# EtherWiz.net
KiCad netlist of a schematic drawn in Altium Designer
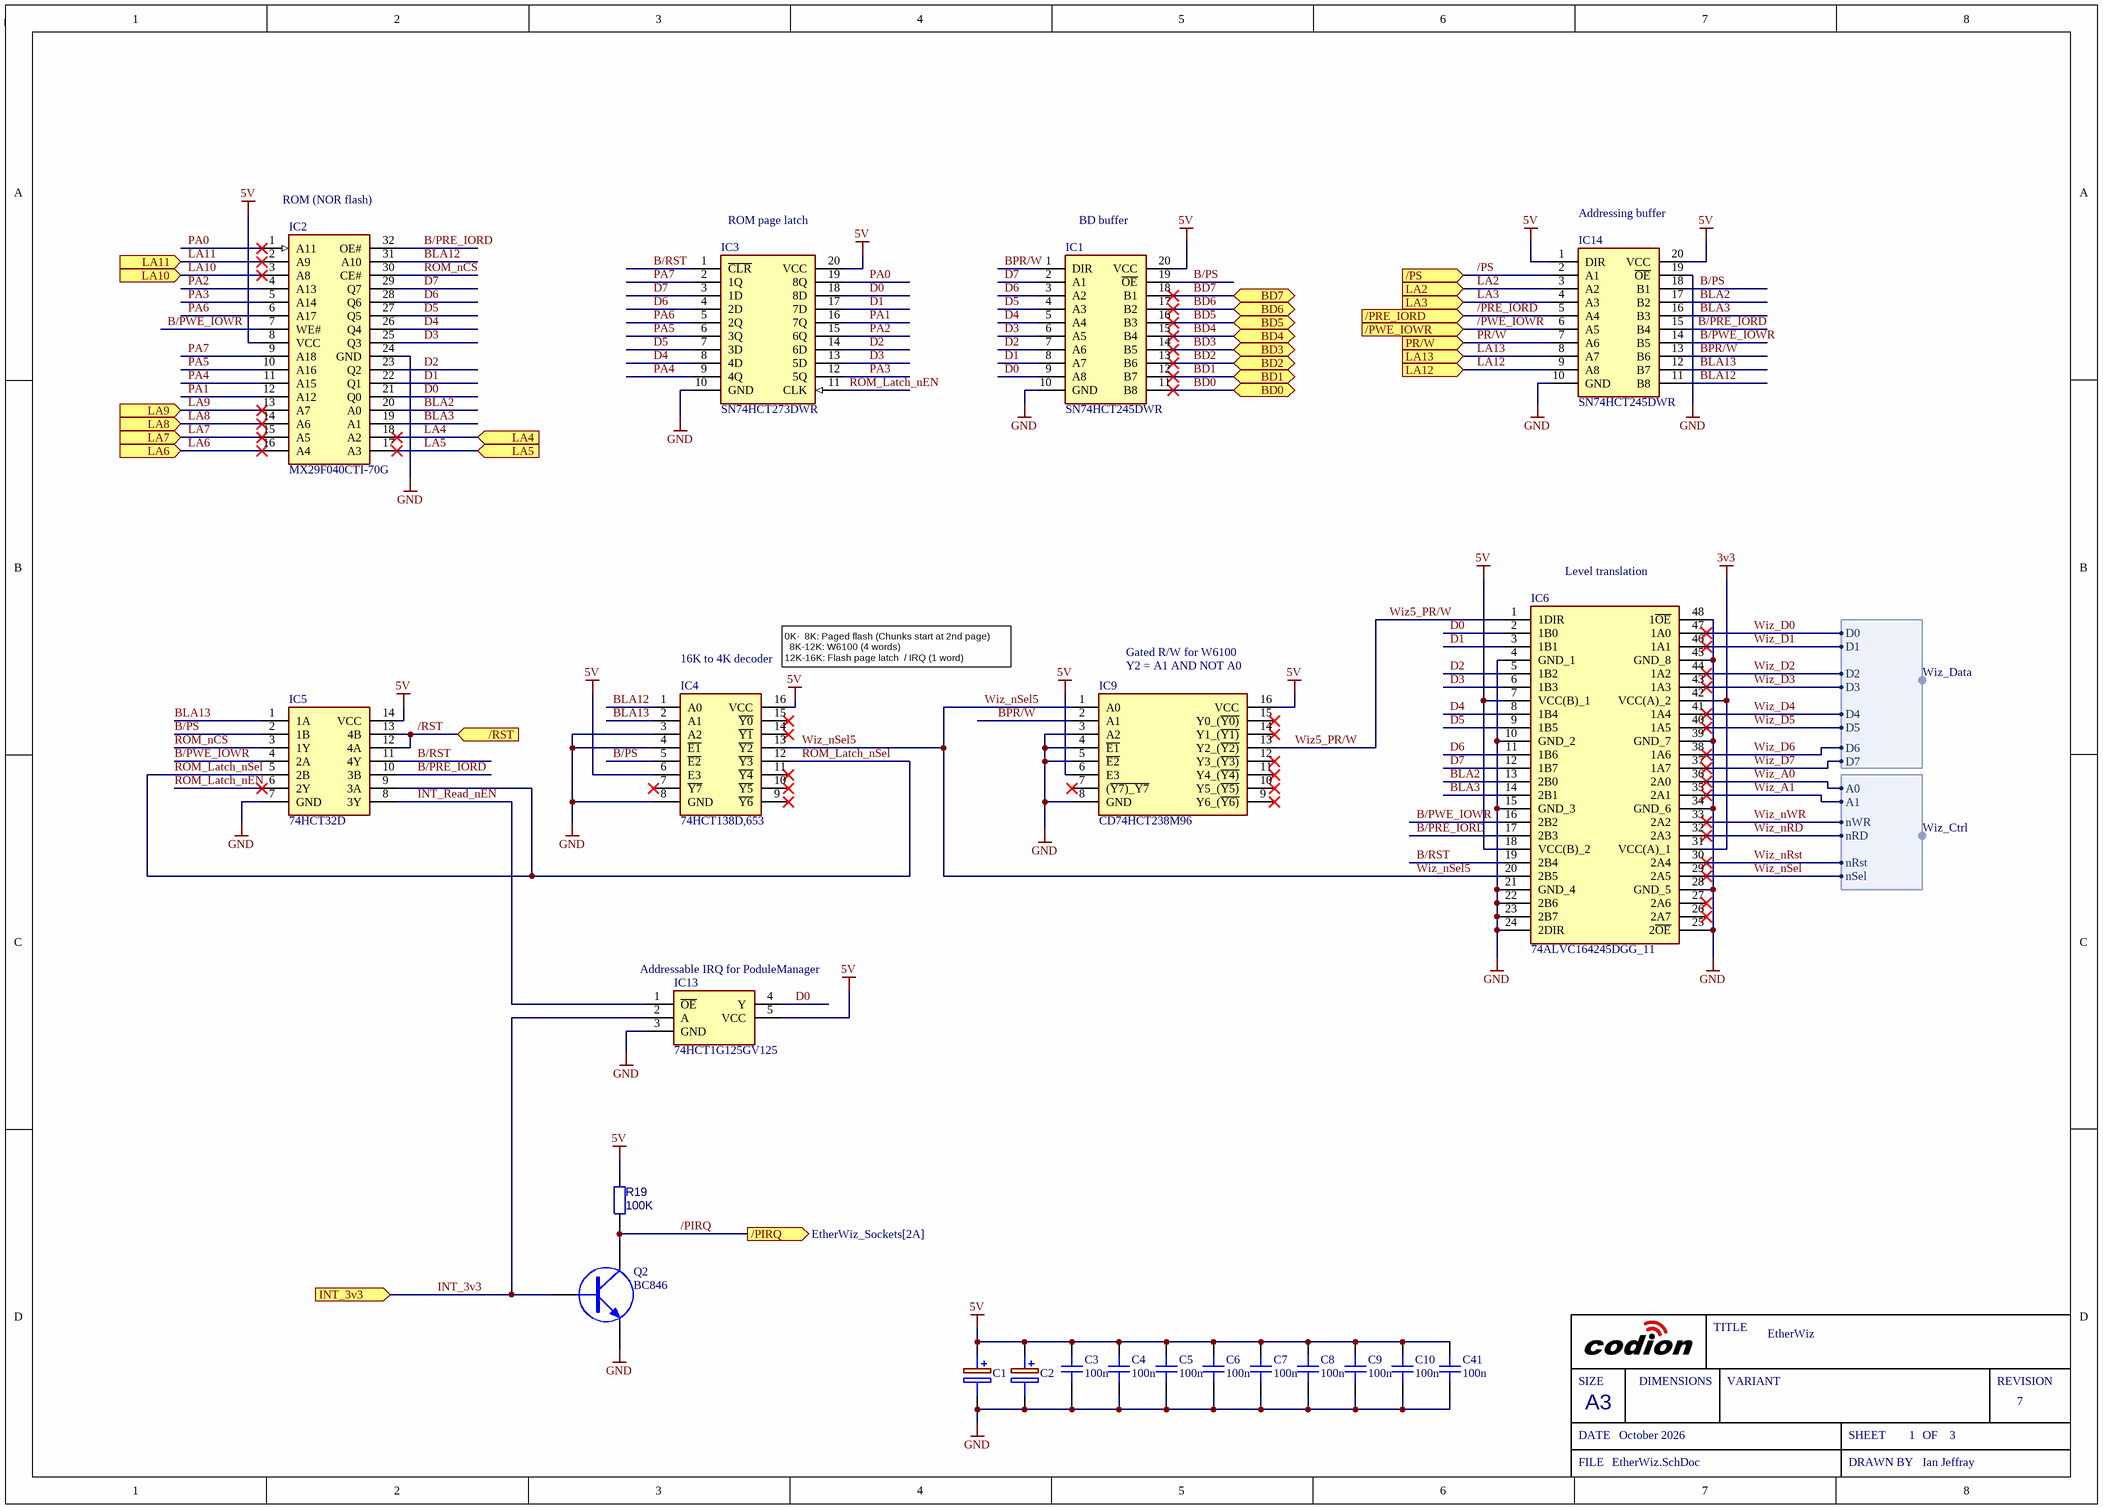
[diagram p0: EtherWiz.SchDoc]

(export (version "E")
  (design (tool "Eeschema 10.0.6"))
  (components
    (comp (ref "C1")
      (value "EEE-HA1C470AP")
      (footprint "SamacSys:EEE1AA101SP")
      (description "Capacitor Polarised")
      (fields (field (name "MOUSER PART NUMBER") "667-EEE-HA1C470AP"))
      (libsource (lib "*") (part "EEE-HA1C470AP"))
    )
    (comp (ref "C2")
      (value "EEE-HA1C470AP")
      (footprint "SamacSys:EEE1AA101SP")
      (description "Capacitor Polarised")
      (fields (field (name "MOUSER PART NUMBER") "667-EEE-HA1C470AP"))
      (libsource (lib "*") (part "EEE-HA1C470AP"))
    )
    (comp (ref "C3")
      (value "100n")
      (footprint "CAPC1608L")
      (description "CAP 100nF, 0603, 50V, X7R, 10%")
      (fields
        (field (name "DISTRIBUTOR1 PART NO") "CL10B104KB8NNNC")
        (field (name "DISTRIBUTOR2 PART NO") "311-1344-2-ND")
      )
      (libsource (lib "MCP1002_RevC") (part "CAP_100n_0603_50V_0"))
    )
    (comp (ref "C4")
      (value "100n")
      (footprint "CAPC1608L")
      (description "CAP 100nF, 0603, 50V, X7R, 10%")
      (fields
        (field (name "DISTRIBUTOR1 PART NO") "CL10B104KB8NNNC")
        (field (name "DISTRIBUTOR2 PART NO") "311-1344-2-ND")
      )
      (libsource (lib "MCP1002_RevC") (part "CAP_100n_0603_50V_0"))
    )
    (comp (ref "C5")
      (value "100n")
      (footprint "CAPC1608L")
      (description "CAP 100nF, 0603, 50V, X7R, 10%")
      (fields
        (field (name "DISTRIBUTOR1 PART NO") "CL10B104KB8NNNC")
        (field (name "DISTRIBUTOR2 PART NO") "311-1344-2-ND")
      )
      (libsource (lib "MCP1002_RevC") (part "CAP_100n_0603_50V_0"))
    )
    (comp (ref "C6")
      (value "100n")
      (footprint "CAPC1608L")
      (description "CAP 100nF, 0603, 50V, X7R, 10%")
      (fields
        (field (name "DISTRIBUTOR1 PART NO") "CL10B104KB8NNNC")
        (field (name "DISTRIBUTOR2 PART NO") "311-1344-2-ND")
      )
      (libsource (lib "MCP1002_RevC") (part "CAP_100n_0603_50V_0"))
    )
    (comp (ref "C7")
      (value "100n")
      (footprint "CAPC1608L")
      (description "CAP 100nF, 0603, 50V, X7R, 10%")
      (fields
        (field (name "DISTRIBUTOR1 PART NO") "CL10B104KB8NNNC")
        (field (name "DISTRIBUTOR2 PART NO") "311-1344-2-ND")
      )
      (libsource (lib "MCP1002_RevC") (part "CAP_100n_0603_50V_0"))
    )
    (comp (ref "C8")
      (value "100n")
      (footprint "CAPC1608L")
      (description "CAP 100nF, 0603, 50V, X7R, 10%")
      (fields
        (field (name "DISTRIBUTOR1 PART NO") "CL10B104KB8NNNC")
        (field (name "DISTRIBUTOR2 PART NO") "311-1344-2-ND")
      )
      (libsource (lib "MCP1002_RevC") (part "CAP_100n_0603_50V_0"))
    )
    (comp (ref "C9")
      (value "100n")
      (footprint "CAPC1608L")
      (description "CAP 100nF, 0603, 50V, X7R, 10%")
      (fields
        (field (name "DISTRIBUTOR1 PART NO") "CL10B104KB8NNNC")
        (field (name "DISTRIBUTOR2 PART NO") "311-1344-2-ND")
      )
      (libsource (lib "MCP1002_RevC") (part "CAP_100n_0603_50V_0"))
    )
    (comp (ref "C10")
      (value "100n")
      (footprint "CAPC1608L")
      (description "CAP 100nF, 0603, 50V, X7R, 10%")
      (fields
        (field (name "DISTRIBUTOR1 PART NO") "CL10B104KB8NNNC")
        (field (name "DISTRIBUTOR2 PART NO") "311-1344-2-ND")
      )
      (libsource (lib "MCP1002_RevC") (part "CAP_100n_0603_50V_0"))
    )
    (comp (ref "C41")
      (value "100n")
      (footprint "CAPC1608L")
      (description "CAP 100nF, 0603, 50V, X7R, 10%")
      (fields
        (field (name "DISTRIBUTOR1 PART NO") "CL10B104KB8NNNC")
        (field (name "DISTRIBUTOR2 PART NO") "311-1344-2-ND")
      )
      (libsource (lib "MCP1002_RevC") (part "CAP_100n_0603_50V_0"))
    )
    (comp (ref "IC1")
      (value "SN74HCT245DWR")
      (footprint "SamacSys:SOIC127P1030X265-20N")
      (description "Integrated Circuit")
      (fields (field (name "MOUSER PART NUMBER") "595-SN74HCT245DWR"))
      (libsource (lib "*") (part "SN74HCT245DWR"))
    )
    (comp (ref "IC2")
      (value "MX29F040CTI-70G")
      (footprint "SamacSys:SOP50P2000X120-32N")
      (description "Integrated Circuit")
      (libsource (lib "*") (part "MX29F040CTI-70G"))
    )
    (comp (ref "IC3")
      (value "SN74HCT273DWR")
      (footprint "SamacSys:SOIC127P1030X265-20N")
      (description "Integrated Circuit")
      (fields (field (name "MOUSER PART NUMBER") "595-SN74HCT273DWR"))
      (libsource (lib "*") (part "SN74HCT273DWR"))
    )
    (comp (ref "IC4")
      (value "74HCT138D,653")
      (footprint "SamacSys:SOIC127P600X175-16N")
      (description "Integrated Circuit")
      (fields (field (name "MOUSER PART NUMBER") "771-74HCT138D-T"))
      (libsource (lib "*") (part "74HCT138D,653"))
    )
    (comp (ref "IC5")
      (value "74HCT32D")
      (footprint "SamacSys:SOIC127P600X175-14N")
      (description "Integrated Circuit")
      (libsource (lib "*") (part "74HCT32D"))
    )
    (comp (ref "IC6")
      (value "74ALVC164245DGG_11")
      (footprint "SamacSys:SOP50P810X120-48N")
      (description "Integrated Circuit")
      (fields
        (field (name "MANUFACTURER_PART_NUMBER") "74ALVC164245DGG:11")
        (field (name "MOUSER PART NUMBER") "771-74ALVC164245")
      )
      (libsource (lib "*") (part "74ALVC164245DGG_11"))
    )
    (comp (ref "IC9")
      (value "CD74HCT238M96")
      (footprint "SamacSys:SOIC127P600X175-16N")
      (description "Integrated Circuit")
      (fields (field (name "MOUSER PART NUMBER") "595-CD74HCT238M96"))
      (libsource (lib "*") (part "CD74HCT238M96"))
    )
    (comp (ref "IC13")
      (value "74HCT1G125GV125")
      (footprint "SamacSys:SOT95P275X110-5N")
      (description "Integrated Circuit")
      (libsource (lib "*") (part "74HCT1G125GV125"))
    )
    (comp (ref "IC14")
      (value "SN74HCT245DWR")
      (footprint "SamacSys:SOIC127P1030X265-20N")
      (description "Integrated Circuit")
      (fields (field (name "MOUSER PART NUMBER") "595-SN74HCT245DWR"))
      (libsource (lib "*") (part "SN74HCT245DWR"))
    )
    (comp (ref "Q2")
      (value "BC846")
      (footprint "SOT-23")
      (description "Transistor NPN, 65V, 100mA, TO-236AB/SOT23")
      (libsource (lib "MCP1002_RevC") (part "TRANS_NPN_BC846_0"))
    )
    (comp (ref "R19")
      (value "100K")
      (footprint "RESC1608X50N")
      (description "Resistor 100K 1%  0603")
      (libsource (lib "Local_Altium_Lib") (part "Resistor - fixed"))
    )
  )
  (nets
    (net (code "1") (name "/BD0") (class "Default")
      (node (ref "IC1") (pin "11") (pinfunction "B8_11") (pintype "passive+no_connect"))
    )
    (net (code "2") (name "/BD1") (class "Default")
      (node (ref "IC1") (pin "12") (pinfunction "B7_12") (pintype "power_in+no_connect"))
    )
    (net (code "3") (name "/BD2") (class "Default")
      (node (ref "IC1") (pin "13") (pinfunction "B6_13") (pintype "passive+no_connect"))
    )
    (net (code "4") (name "/BD3") (class "Default")
      (node (ref "IC1") (pin "14") (pinfunction "B5_14") (pintype "passive+no_connect"))
    )
    (net (code "5") (name "/BD4") (class "Default")
      (node (ref "IC1") (pin "15") (pinfunction "B4_15") (pintype "passive+no_connect"))
    )
    (net (code "6") (name "/BD5") (class "Default")
      (node (ref "IC1") (pin "16") (pinfunction "B3_16") (pintype "passive+no_connect"))
    )
    (net (code "7") (name "/BD6") (class "Default")
      (node (ref "IC1") (pin "17") (pinfunction "B2_17") (pintype "passive+no_connect"))
    )
    (net (code "8") (name "/BD7") (class "Default")
      (node (ref "IC1") (pin "18") (pinfunction "B1_18") (pintype "passive+no_connect"))
    )
    (net (code "9") (name "/BLA2") (class "Default")
      (node (ref "IC14") (pin "17") (pinfunction "B2_17") (pintype "passive"))
      (node (ref "IC2") (pin "20") (pinfunction "A0_20") (pintype "passive"))
      (node (ref "IC6") (pin "13") (pinfunction "2B0_13") (pintype "passive"))
    )
    (net (code "10") (name "/BLA3") (class "Default")
      (node (ref "IC14") (pin "16") (pinfunction "B3_16") (pintype "passive"))
      (node (ref "IC2") (pin "19") (pinfunction "A1_19") (pintype "passive"))
      (node (ref "IC6") (pin "14") (pinfunction "2B1_14") (pintype "passive"))
    )
    (net (code "11") (name "/BLA12") (class "Default")
      (node (ref "IC14") (pin "11") (pinfunction "B8_11") (pintype "passive"))
      (node (ref "IC2") (pin "31") (pinfunction "A10_31") (pintype "passive"))
      (node (ref "IC4") (pin "1") (pinfunction "A0_1") (pintype "passive"))
    )
    (net (code "12") (name "/BLA13") (class "Default")
      (node (ref "IC14") (pin "12") (pinfunction "B7_12") (pintype "power_in"))
      (node (ref "IC4") (pin "2") (pinfunction "A1_2") (pintype "passive"))
      (node (ref "IC5") (pin "1") (pinfunction "1A_1") (pintype "passive"))
    )
    (net (code "13") (name "/BPR{slash}W") (class "Default")
      (node (ref "IC1") (pin "1") (pinfunction "DIR_1") (pintype "passive"))
      (node (ref "IC14") (pin "13") (pinfunction "B6_13") (pintype "passive"))
      (node (ref "IC9") (pin "2") (pinfunction "A1_2") (pintype "passive"))
    )
    (net (code "14") (name "/B{slash}PRE_IORD") (class "Default")
      (node (ref "IC14") (pin "15") (pinfunction "B4_15") (pintype "passive"))
      (node (ref "IC2") (pin "32") (pinfunction "OE#_32") (pintype "passive"))
      (node (ref "IC5") (pin "10") (pinfunction "3B_10") (pintype "passive"))
      (node (ref "IC6") (pin "17") (pinfunction "2B3_17") (pintype "passive"))
    )
    (net (code "15") (name "/B{slash}PS") (class "Default")
      (node (ref "IC1") (pin "19") (pinfunction "~{OE}_19") (pintype "passive"))
      (node (ref "IC14") (pin "18") (pinfunction "B1_18") (pintype "passive"))
      (node (ref "IC4") (pin "5") (pinfunction "~{E2}_5") (pintype "passive"))
      (node (ref "IC5") (pin "2") (pinfunction "1B_2") (pintype "passive"))
    )
    (net (code "16") (name "/B{slash}PWE_IOWR") (class "Default")
      (node (ref "IC14") (pin "14") (pinfunction "B5_14") (pintype "passive"))
      (node (ref "IC2") (pin "7") (pinfunction "WE#_7") (pintype "passive"))
      (node (ref "IC5") (pin "4") (pinfunction "2A_4") (pintype "passive"))
      (node (ref "IC6") (pin "16") (pinfunction "2B2_16") (pintype "passive"))
    )
    (net (code "17") (name "/B{slash}RST") (class "Default")
      (node (ref "IC3") (pin "1") (pinfunction "~{CLR}_1") (pintype "passive"))
      (node (ref "IC5") (pin "11") (pinfunction "4Y_11") (pintype "passive"))
      (node (ref "IC6") (pin "19") (pinfunction "2B4_19") (pintype "passive"))
    )
    (net (code "18") (name "/D0") (class "Default")
      (node (ref "IC1") (pin "9") (pinfunction "A8_9") (pintype "passive"))
      (node (ref "IC13") (pin "4") (pinfunction "Y_4") (pintype "passive"))
      (node (ref "IC2") (pin "21") (pinfunction "Q0_21") (pintype "passive"))
      (node (ref "IC3") (pin "18") (pinfunction "8D_18") (pintype "passive"))
      (node (ref "IC6") (pin "2") (pinfunction "1B0_2") (pintype "passive"))
    )
    (net (code "19") (name "/D1") (class "Default")
      (node (ref "IC1") (pin "8") (pinfunction "A7_8") (pintype "passive"))
      (node (ref "IC2") (pin "22") (pinfunction "Q1_22") (pintype "passive"))
      (node (ref "IC3") (pin "17") (pinfunction "7D_17") (pintype "passive"))
      (node (ref "IC6") (pin "3") (pinfunction "1B1_3") (pintype "passive"))
    )
    (net (code "20") (name "/D2") (class "Default")
      (node (ref "IC1") (pin "7") (pinfunction "A6_7") (pintype "passive"))
      (node (ref "IC2") (pin "23") (pinfunction "Q2_23") (pintype "passive"))
      (node (ref "IC3") (pin "14") (pinfunction "6D_14") (pintype "passive"))
      (node (ref "IC6") (pin "5") (pinfunction "1B2_5") (pintype "passive"))
    )
    (net (code "21") (name "/D3") (class "Default")
      (node (ref "IC1") (pin "6") (pinfunction "A5_6") (pintype "passive"))
      (node (ref "IC2") (pin "25") (pinfunction "Q3_25") (pintype "passive"))
      (node (ref "IC3") (pin "13") (pinfunction "5D_13") (pintype "passive"))
      (node (ref "IC6") (pin "6") (pinfunction "1B3_6") (pintype "passive"))
    )
    (net (code "22") (name "/D4") (class "Default")
      (node (ref "IC1") (pin "5") (pinfunction "A4_5") (pintype "passive"))
      (node (ref "IC2") (pin "26") (pinfunction "Q4_26") (pintype "passive"))
      (node (ref "IC3") (pin "8") (pinfunction "4D_8") (pintype "passive"))
      (node (ref "IC6") (pin "8") (pinfunction "1B4_8") (pintype "passive"))
    )
    (net (code "23") (name "/D5") (class "Default")
      (node (ref "IC1") (pin "4") (pinfunction "A3_4") (pintype "passive"))
      (node (ref "IC2") (pin "27") (pinfunction "Q5_27") (pintype "passive"))
      (node (ref "IC3") (pin "7") (pinfunction "3D_7") (pintype "passive"))
      (node (ref "IC6") (pin "9") (pinfunction "1B5_9") (pintype "passive"))
    )
    (net (code "24") (name "/D6") (class "Default")
      (node (ref "IC1") (pin "3") (pinfunction "A2_3") (pintype "passive"))
      (node (ref "IC2") (pin "28") (pinfunction "Q6_28") (pintype "passive"))
      (node (ref "IC3") (pin "4") (pinfunction "2D_4") (pintype "passive"))
      (node (ref "IC6") (pin "11") (pinfunction "1B6_11") (pintype "passive"))
    )
    (net (code "25") (name "/D7") (class "Default")
      (node (ref "IC1") (pin "2") (pinfunction "A1_2") (pintype "passive"))
      (node (ref "IC2") (pin "29") (pinfunction "Q7_29") (pintype "passive"))
      (node (ref "IC3") (pin "3") (pinfunction "1D_3") (pintype "passive"))
      (node (ref "IC6") (pin "12") (pinfunction "1B7_12") (pintype "passive"))
    )
    (net (code "26") (name "/INT_3v3") (class "Default")
      (node (ref "IC13") (pin "2") (pinfunction "A_2") (pintype "passive"))
      (node (ref "Q2") (pin "1") (pinfunction "B_1") (pintype "passive"))
    )
    (net (code "27") (name "/INT_Read_nEN") (class "Default")
      (node (ref "IC13") (pin "1") (pinfunction "~{OE}_1") (pintype "passive"))
      (node (ref "IC5") (pin "8") (pinfunction "3Y_8") (pintype "passive"))
    )
    (net (code "28") (name "/LA2") (class "Default")
      (node (ref "IC14") (pin "3") (pinfunction "A2_3") (pintype "passive"))
    )
    (net (code "29") (name "/LA3") (class "Default")
      (node (ref "IC14") (pin "4") (pinfunction "A3_4") (pintype "passive"))
    )
    (net (code "30") (name "/LA4") (class "Default")
      (node (ref "IC2") (pin "18") (pinfunction "A2_18") (pintype "passive+no_connect"))
    )
    (net (code "31") (name "/LA5") (class "Default")
      (node (ref "IC2") (pin "17") (pinfunction "A3_17") (pintype "passive+no_connect"))
    )
    (net (code "32") (name "/LA6") (class "Default")
      (node (ref "IC2") (pin "16") (pinfunction "A4_16") (pintype "passive+no_connect"))
    )
    (net (code "33") (name "/LA7") (class "Default")
      (node (ref "IC2") (pin "15") (pinfunction "A5_15") (pintype "passive+no_connect"))
    )
    (net (code "34") (name "/LA8") (class "Default")
      (node (ref "IC2") (pin "14") (pinfunction "A6_14") (pintype "passive+no_connect"))
    )
    (net (code "35") (name "/LA9") (class "Default")
      (node (ref "IC2") (pin "13") (pinfunction "A7_13") (pintype "passive+no_connect"))
    )
    (net (code "36") (name "/LA10") (class "Default")
      (node (ref "IC2") (pin "3") (pinfunction "A8_3") (pintype "passive+no_connect"))
    )
    (net (code "37") (name "/LA11") (class "Default")
      (node (ref "IC2") (pin "2") (pinfunction "A9_2") (pintype "passive+no_connect"))
    )
    (net (code "38") (name "/LA12") (class "Default")
      (node (ref "IC14") (pin "9") (pinfunction "A8_9") (pintype "passive"))
    )
    (net (code "39") (name "/LA13") (class "Default")
      (node (ref "IC14") (pin "8") (pinfunction "A7_8") (pintype "passive"))
    )
    (net (code "40") (name "/PA0") (class "Default")
      (node (ref "IC2") (pin "1") (pinfunction "A11_1") (pintype "input"))
      (node (ref "IC3") (pin "19") (pinfunction "8Q_19") (pintype "passive"))
    )
    (net (code "41") (name "/PA1") (class "Default")
      (node (ref "IC2") (pin "12") (pinfunction "A12_12") (pintype "passive"))
      (node (ref "IC3") (pin "16") (pinfunction "7Q_16") (pintype "passive"))
    )
    (net (code "42") (name "/PA2") (class "Default")
      (node (ref "IC2") (pin "4") (pinfunction "A13_4") (pintype "passive"))
      (node (ref "IC3") (pin "15") (pinfunction "6Q_15") (pintype "passive"))
    )
    (net (code "43") (name "/PA3") (class "Default")
      (node (ref "IC2") (pin "5") (pinfunction "A14_5") (pintype "passive"))
      (node (ref "IC3") (pin "12") (pinfunction "5Q_12") (pintype "passive"))
    )
    (net (code "44") (name "/PA4") (class "Default")
      (node (ref "IC2") (pin "11") (pinfunction "A15_11") (pintype "passive"))
      (node (ref "IC3") (pin "9") (pinfunction "4Q_9") (pintype "passive"))
    )
    (net (code "45") (name "/PA5") (class "Default")
      (node (ref "IC2") (pin "10") (pinfunction "A16_10") (pintype "passive"))
      (node (ref "IC3") (pin "6") (pinfunction "3Q_6") (pintype "passive"))
    )
    (net (code "46") (name "/PA6") (class "Default")
      (node (ref "IC2") (pin "6") (pinfunction "A17_6") (pintype "passive"))
      (node (ref "IC3") (pin "5") (pinfunction "2Q_5") (pintype "passive"))
    )
    (net (code "47") (name "/PA7") (class "Default")
      (node (ref "IC2") (pin "9") (pinfunction "A18_9") (pintype "passive"))
      (node (ref "IC3") (pin "2") (pinfunction "1Q_2") (pintype "passive"))
    )
    (net (code "48") (name "/PR{slash}W") (class "Default")
      (node (ref "IC14") (pin "7") (pinfunction "A6_7") (pintype "passive"))
    )
    (net (code "49") (name "/ROM_Latch_nEN") (class "Default")
      (node (ref "IC3") (pin "11") (pinfunction "CLK_11") (pintype "input"))
      (node (ref "IC5") (pin "6") (pinfunction "2Y_6") (pintype "passive"))
    )
    (net (code "50") (name "/ROM_Latch_nSel") (class "Default")
      (node (ref "IC4") (pin "12") (pinfunction "~{Y3}_12") (pintype "passive"))
      (node (ref "IC5") (pin "5") (pinfunction "2B_5") (pintype "passive"))
      (node (ref "IC5") (pin "9") (pinfunction "3A_9") (pintype "passive"))
    )
    (net (code "51") (name "/ROM_nCS") (class "Default")
      (node (ref "IC2") (pin "30") (pinfunction "CE#_30") (pintype "passive"))
      (node (ref "IC5") (pin "3") (pinfunction "1Y_3") (pintype "passive"))
    )
    (net (code "52") (name "/Wiz5_PR{slash}W") (class "Default")
      (node (ref "IC6") (pin "1") (pinfunction "1DIR_1") (pintype "passive"))
      (node (ref "IC9") (pin "13") (pinfunction "Y2_(~{Y2)}_13") (pintype "passive"))
    )
    (net (code "53") (name "/Wiz_A0") (class "Default")
      (node (ref "IC6") (pin "36") (pinfunction "2A0_36") (pintype "passive+no_connect"))
    )
    (net (code "54") (name "/Wiz_A1") (class "Default")
      (node (ref "IC6") (pin "35") (pinfunction "2A1_35") (pintype "passive+no_connect"))
    )
    (net (code "55") (name "/Wiz_D0") (class "Default")
      (node (ref "IC6") (pin "47") (pinfunction "1A0_47") (pintype "passive+no_connect"))
    )
    (net (code "56") (name "/Wiz_D1") (class "Default")
      (node (ref "IC6") (pin "46") (pinfunction "1A1_46") (pintype "passive+no_connect"))
    )
    (net (code "57") (name "/Wiz_D2") (class "Default")
      (node (ref "IC6") (pin "44") (pinfunction "1A2_44") (pintype "passive+no_connect"))
    )
    (net (code "58") (name "/Wiz_D3") (class "Default")
      (node (ref "IC6") (pin "43") (pinfunction "1A3_43") (pintype "passive+no_connect"))
    )
    (net (code "59") (name "/Wiz_D4") (class "Default")
      (node (ref "IC6") (pin "41") (pinfunction "1A4_41") (pintype "passive+no_connect"))
    )
    (net (code "60") (name "/Wiz_D5") (class "Default")
      (node (ref "IC6") (pin "40") (pinfunction "1A5_40") (pintype "passive+no_connect"))
    )
    (net (code "61") (name "/Wiz_D6") (class "Default")
      (node (ref "IC6") (pin "38") (pinfunction "1A6_38") (pintype "passive+no_connect"))
    )
    (net (code "62") (name "/Wiz_D7") (class "Default")
      (node (ref "IC6") (pin "37") (pinfunction "1A7_37") (pintype "passive+no_connect"))
    )
    (net (code "63") (name "/Wiz_nRD") (class "Default")
      (node (ref "IC6") (pin "32") (pinfunction "2A3_32") (pintype "passive+no_connect"))
    )
    (net (code "64") (name "/Wiz_nRst") (class "Default")
      (node (ref "IC6") (pin "30") (pinfunction "2A4_30") (pintype "passive+no_connect"))
    )
    (net (code "65") (name "/Wiz_nSel") (class "Default")
      (node (ref "IC6") (pin "29") (pinfunction "2A5_29") (pintype "passive+no_connect"))
    )
    (net (code "66") (name "/Wiz_nSel5") (class "Default")
      (node (ref "IC4") (pin "13") (pinfunction "~{Y2}_13") (pintype "passive"))
      (node (ref "IC6") (pin "20") (pinfunction "2B5_20") (pintype "passive"))
      (node (ref "IC9") (pin "1") (pinfunction "A0_1") (pintype "passive"))
    )
    (net (code "67") (name "/Wiz_nWR") (class "Default")
      (node (ref "IC6") (pin "33") (pinfunction "2A2_33") (pintype "passive+no_connect"))
    )
    (net (code "68") (name "/{slash}PIRQ") (class "Default")
      (node (ref "Q2") (pin "3") (pinfunction "C_3") (pintype "passive"))
      (node (ref "R19") (pin "1") (pinfunction "1_1") (pintype "passive"))
    )
    (net (code "69") (name "/{slash}PRE_IORD") (class "Default")
      (node (ref "IC14") (pin "5") (pinfunction "A4_5") (pintype "passive"))
    )
    (net (code "70") (name "/{slash}PS") (class "Default")
      (node (ref "IC14") (pin "2") (pinfunction "A1_2") (pintype "passive"))
    )
    (net (code "71") (name "/{slash}PWE_IOWR") (class "Default")
      (node (ref "IC14") (pin "6") (pinfunction "A5_6") (pintype "passive"))
    )
    (net (code "72") (name "/{slash}RST") (class "Default")
      (node (ref "IC5") (pin "12") (pinfunction "4A_12") (pintype "passive"))
      (node (ref "IC5") (pin "13") (pinfunction "4B_13") (pintype "passive"))
    )
    (net (code "73") (name "3v3") (class "Default")
      (node (ref "IC6") (pin "31") (pinfunction "VCC(A)_1_31") (pintype "passive"))
      (node (ref "IC6") (pin "42") (pinfunction "VCC(A)_2_42") (pintype "passive"))
    )
    (net (code "74") (name "5V") (class "Default")
      (node (ref "C1") (pin "1") (pinfunction "+_1") (pintype "passive"))
      (node (ref "C10") (pin "2") (pintype "passive"))
      (node (ref "C2") (pin "1") (pinfunction "+_1") (pintype "passive"))
      (node (ref "C3") (pin "2") (pintype "passive"))
      (node (ref "C4") (pin "2") (pintype "passive"))
      (node (ref "C41") (pin "2") (pintype "passive"))
      (node (ref "C5") (pin "2") (pintype "passive"))
      (node (ref "C6") (pin "2") (pintype "passive"))
      (node (ref "C7") (pin "2") (pintype "passive"))
      (node (ref "C8") (pin "2") (pintype "passive"))
      (node (ref "C9") (pin "2") (pintype "passive"))
      (node (ref "IC1") (pin "20") (pinfunction "VCC_20") (pintype "power_in"))
      (node (ref "IC13") (pin "5") (pinfunction "VCC_5") (pintype "passive"))
      (node (ref "IC14") (pin "1") (pinfunction "DIR_1") (pintype "passive"))
      (node (ref "IC14") (pin "20") (pinfunction "VCC_20") (pintype "power_in"))
      (node (ref "IC2") (pin "8") (pinfunction "VCC_8") (pintype "passive"))
      (node (ref "IC3") (pin "20") (pinfunction "VCC_20") (pintype "power_in"))
      (node (ref "IC4") (pin "16") (pinfunction "VCC_16") (pintype "passive"))
      (node (ref "IC4") (pin "6") (pinfunction "E3_6") (pintype "passive"))
      (node (ref "IC5") (pin "14") (pinfunction "VCC_14") (pintype "passive"))
      (node (ref "IC6") (pin "18") (pinfunction "VCC(B)_2_18") (pintype "passive"))
      (node (ref "IC6") (pin "7") (pinfunction "VCC(B)_1_7") (pintype "passive"))
      (node (ref "IC9") (pin "16") (pinfunction "VCC_16") (pintype "passive"))
      (node (ref "IC9") (pin "6") (pinfunction "E3_6") (pintype "passive"))
      (node (ref "R19") (pin "2") (pinfunction "2_2") (pintype "passive"))
    )
    (net (code "75") (name "GND") (class "Default")
      (node (ref "C1") (pin "2") (pinfunction "-_2") (pintype "passive"))
      (node (ref "C10") (pin "1") (pintype "passive"))
      (node (ref "C2") (pin "2") (pinfunction "-_2") (pintype "passive"))
      (node (ref "C3") (pin "1") (pintype "passive"))
      (node (ref "C4") (pin "1") (pintype "passive"))
      (node (ref "C41") (pin "1") (pintype "passive"))
      (node (ref "C5") (pin "1") (pintype "passive"))
      (node (ref "C6") (pin "1") (pintype "passive"))
      (node (ref "C7") (pin "1") (pintype "passive"))
      (node (ref "C8") (pin "1") (pintype "passive"))
      (node (ref "C9") (pin "1") (pintype "passive"))
      (node (ref "IC1") (pin "10") (pinfunction "GND_10") (pintype "power_in"))
      (node (ref "IC13") (pin "3") (pinfunction "GND_3") (pintype "passive"))
      (node (ref "IC14") (pin "10") (pinfunction "GND_10") (pintype "power_in"))
      (node (ref "IC14") (pin "19") (pinfunction "~{OE}_19") (pintype "passive"))
      (node (ref "IC2") (pin "24") (pinfunction "GND_24") (pintype "passive"))
      (node (ref "IC3") (pin "10") (pinfunction "GND_10") (pintype "power_in"))
      (node (ref "IC4") (pin "3") (pinfunction "A2_3") (pintype "passive"))
      (node (ref "IC4") (pin "4") (pinfunction "~{E1}_4") (pintype "passive"))
      (node (ref "IC4") (pin "8") (pinfunction "GND_8") (pintype "passive"))
      (node (ref "IC5") (pin "7") (pinfunction "GND_7") (pintype "passive"))
      (node (ref "IC6") (pin "10") (pinfunction "GND_2_10") (pintype "passive"))
      (node (ref "IC6") (pin "15") (pinfunction "GND_3_15") (pintype "passive"))
      (node (ref "IC6") (pin "21") (pinfunction "GND_4_21") (pintype "passive"))
      (node (ref "IC6") (pin "22") (pinfunction "2B6_22") (pintype "passive"))
      (node (ref "IC6") (pin "23") (pinfunction "2B7_23") (pintype "passive"))
      (node (ref "IC6") (pin "24") (pinfunction "2DIR_24") (pintype "passive"))
      (node (ref "IC6") (pin "25") (pinfunction "2~{OE}_25") (pintype "passive"))
      (node (ref "IC6") (pin "28") (pinfunction "GND_5_28") (pintype "passive"))
      (node (ref "IC6") (pin "34") (pinfunction "GND_6_34") (pintype "passive"))
      (node (ref "IC6") (pin "39") (pinfunction "GND_7_39") (pintype "passive"))
      (node (ref "IC6") (pin "4") (pinfunction "GND_1_4") (pintype "passive"))
      (node (ref "IC6") (pin "45") (pinfunction "GND_8_45") (pintype "passive"))
      (node (ref "IC6") (pin "48") (pinfunction "1~{OE}_48") (pintype "passive"))
      (node (ref "IC9") (pin "3") (pinfunction "A2_3") (pintype "passive"))
      (node (ref "IC9") (pin "4") (pinfunction "~{E1}_4") (pintype "passive"))
      (node (ref "IC9") (pin "5") (pinfunction "~{E2}_5") (pintype "passive"))
      (node (ref "IC9") (pin "8") (pinfunction "GND_8") (pintype "passive"))
      (node (ref "Q2") (pin "2") (pinfunction "E_2") (pintype "passive"))
    )
    (net (code "76") (name "unconnected-(IC4-~{Y0}-Pad15)") (class "Default")
      (node (ref "IC4") (pin "15") (pinfunction "~{Y0}_15") (pintype "passive+no_connect"))
    )
    (net (code "77") (name "unconnected-(IC4-~{Y1}-Pad14)") (class "Default")
      (node (ref "IC4") (pin "14") (pinfunction "~{Y1}_14") (pintype "passive+no_connect"))
    )
    (net (code "78") (name "unconnected-(IC4-~{Y4}-Pad11)") (class "Default")
      (node (ref "IC4") (pin "11") (pinfunction "~{Y4}_11") (pintype "passive+no_connect"))
    )
    (net (code "79") (name "unconnected-(IC4-~{Y5}-Pad10)") (class "Default")
      (node (ref "IC4") (pin "10") (pinfunction "~{Y5}_10") (pintype "passive+no_connect"))
    )
    (net (code "80") (name "unconnected-(IC4-~{Y6}-Pad9)") (class "Default")
      (node (ref "IC4") (pin "9") (pinfunction "~{Y6}_9") (pintype "passive+no_connect"))
    )
    (net (code "81") (name "unconnected-(IC4-~{Y7}-Pad7)") (class "Default")
      (node (ref "IC4") (pin "7") (pinfunction "~{Y7}_7") (pintype "passive+no_connect"))
    )
    (net (code "82") (name "unconnected-(IC6-2A6-Pad27)") (class "Default")
      (node (ref "IC6") (pin "27") (pinfunction "2A6_27") (pintype "passive+no_connect"))
    )
    (net (code "83") (name "unconnected-(IC6-2A7-Pad26)") (class "Default")
      (node (ref "IC6") (pin "26") (pinfunction "2A7_26") (pintype "passive+no_connect"))
    )
    (net (code "84") (name "unconnected-(IC9-(~{Y7)_Y7}-Pad7)") (class "Default")
      (node (ref "IC9") (pin "7") (pinfunction "(~{Y7)_Y7}_7") (pintype "passive+no_connect"))
    )
    (net (code "85") (name "unconnected-(IC9-Y0_(~{Y0)}-Pad15)") (class "Default")
      (node (ref "IC9") (pin "15") (pinfunction "Y0_(~{Y0)}_15") (pintype "passive+no_connect"))
    )
    (net (code "86") (name "unconnected-(IC9-Y1_(~{Y1)}-Pad14)") (class "Default")
      (node (ref "IC9") (pin "14") (pinfunction "Y1_(~{Y1)}_14") (pintype "passive+no_connect"))
    )
    (net (code "87") (name "unconnected-(IC9-Y3_(~{Y3)}-Pad12)") (class "Default")
      (node (ref "IC9") (pin "12") (pinfunction "Y3_(~{Y3)}_12") (pintype "passive+no_connect"))
    )
    (net (code "88") (name "unconnected-(IC9-Y4_(~{Y4)}-Pad11)") (class "Default")
      (node (ref "IC9") (pin "11") (pinfunction "Y4_(~{Y4)}_11") (pintype "passive+no_connect"))
    )
    (net (code "89") (name "unconnected-(IC9-Y5_(~{Y5)}-Pad10)") (class "Default")
      (node (ref "IC9") (pin "10") (pinfunction "Y5_(~{Y5)}_10") (pintype "passive+no_connect"))
    )
    (net (code "90") (name "unconnected-(IC9-Y6_(~{Y6)}-Pad9)") (class "Default")
      (node (ref "IC9") (pin "9") (pinfunction "Y6_(~{Y6)}_9") (pintype "passive+no_connect"))
    )
  )
)
